# RELAY.net
KiCad netlist of a schematic drawn in Altium Designer
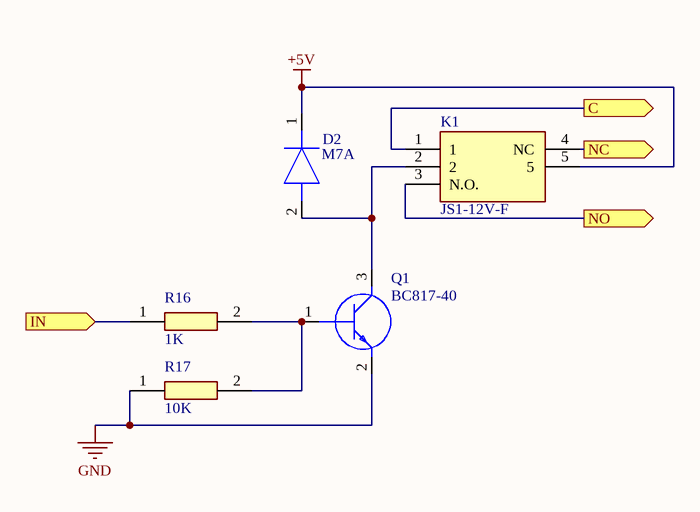
[diagram p0: RELAY.SchDoc]

(export (version "E")
  (design (tool "Eeschema 10.0.6"))
  (components
    (comp (ref "D2")
      (value "M7A")
      (footprint "SamacSys:DIOM5027X262N")
      (description "Diode")
      (libsource (lib "*") (part "M7A"))
    )
    (comp (ref "K1")
      (value "JS1-12V-F")
      (footprint "SamacSys:JS1-12V-F_1")
      (description "Relay or Contactor")
      (fields (field (name "MOUSER PART NUMBER") "769-JS1-12V-F"))
      (libsource (lib "*") (part "JS1-12V-F"))
    )
    (comp (ref "Q1")
      (value "BC817-40")
      (footprint "SamacSys:BC81740215")
      (description "Transistor BJT NPN")
      (fields
        (field (name "MANUFACTURER_PART_NUMBER") "BC817-40,215")
        (field (name "MOUSER PART NUMBER") "771-BC817-40-T/R")
      )
      (libsource (lib "*") (part "BC817-40,215"))
    )
    (comp (ref "R16")
      (value "1K")
      (footprint "SamacSys:RESC3216X75N")
      (description "Resistor")
      (fields
        (field (name "MANUFACTURER_PART_NUMBER") "CR1206-F/-2R00ELF")
        (field (name "MOUSER PART NUMBER") "652-CR1206-F/2R00ELF")
      )
      (libsource (lib "*") (part "CR1206-F_-2R00ELF"))
    )
    (comp (ref "R17")
      (value "10K")
      (footprint "SamacSys:RESC3216X75N")
      (description "Resistor")
      (fields
        (field (name "MANUFACTURER_PART_NUMBER") "CR1206-F/-2R00ELF")
        (field (name "MOUSER PART NUMBER") "652-CR1206-F/2R00ELF")
      )
      (libsource (lib "*") (part "CR1206-F_-2R00ELF"))
    )
  )
  (nets
    (net (code "1") (name "+5V") (class "Default")
      (node (ref "D2") (pin "1") (pinfunction "K_1") (pintype "passive"))
      (node (ref "K1") (pin "5") (pinfunction "5_5") (pintype "passive"))
    )
    (net (code "2") (name "/C") (class "Default")
      (node (ref "K1") (pin "1") (pinfunction "1_1") (pintype "passive"))
    )
    (net (code "3") (name "/IN") (class "Default")
      (node (ref "R16") (pin "1") (pinfunction "1_1") (pintype "passive"))
    )
    (net (code "4") (name "/NC") (class "Default")
      (node (ref "K1") (pin "4") (pinfunction "NC_4") (pintype "passive"))
    )
    (net (code "5") (name "/NO") (class "Default")
      (node (ref "K1") (pin "3") (pinfunction "N.O._3") (pintype "passive"))
    )
    (net (code "6") (name "GND") (class "Default")
      (node (ref "Q1") (pin "2") (pinfunction "E_2") (pintype "passive"))
      (node (ref "R17") (pin "1") (pinfunction "1_1") (pintype "passive"))
    )
    (net (code "7") (name "Net-(D2-A)") (class "Default")
      (node (ref "D2") (pin "2") (pinfunction "A_2") (pintype "passive"))
      (node (ref "K1") (pin "2") (pinfunction "2_2") (pintype "passive"))
      (node (ref "Q1") (pin "3") (pinfunction "C_3") (pintype "passive"))
    )
    (net (code "8") (name "Net-(Q1-B)") (class "Default")
      (node (ref "Q1") (pin "1") (pinfunction "B_1") (pintype "passive"))
      (node (ref "R16") (pin "2") (pinfunction "2_2") (pintype "passive"))
      (node (ref "R17") (pin "2") (pinfunction "2_2") (pintype "passive"))
    )
  )
)
